# gps.net
KiCad netlist of a schematic drawn in Altium Designer
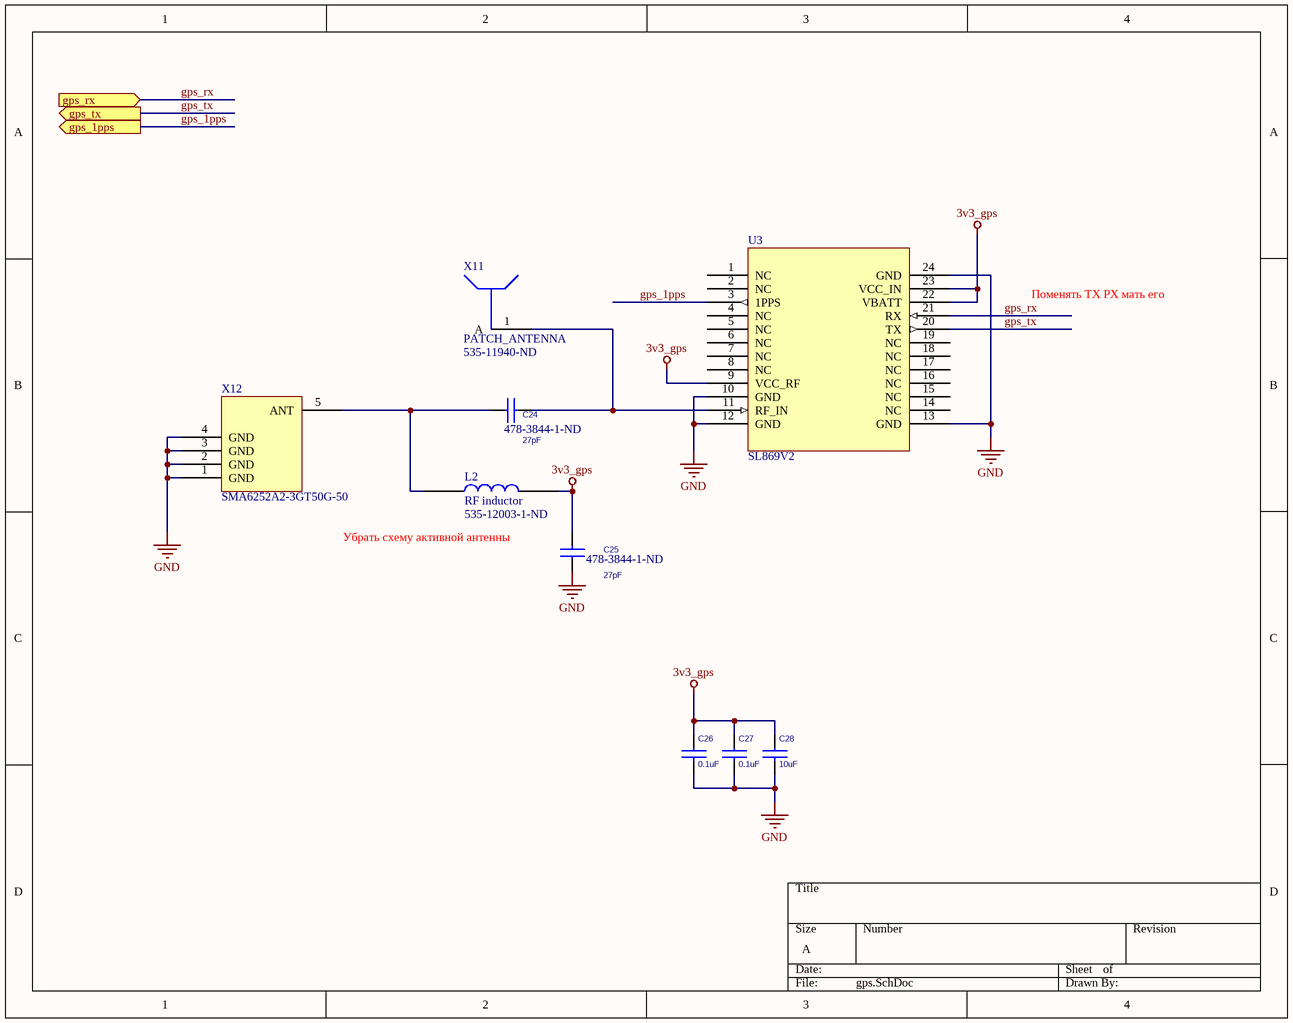
[diagram p0: gps.SchDoc]

(export (version "E")
  (design (tool "Eeschema 10.0.6"))
  (components
    (comp (ref "C24")
      (value "27pF")
      (footprint "CAPC2012X09M")
      (description "CAP CER 27PF 200V 5% NP0 0805")
      (fields (field (name "SUPPLIER PART NUMBER 1") "478-3844-1-ND"))
      (libsource (lib "Capacitors") (part "CAP_SMD_27PF_5%"))
    )
    (comp (ref "C25")
      (value "27pF")
      (footprint "CAPC2012X09M")
      (description "CAP CER 27PF 200V 5% NP0 0805")
      (fields (field (name "SUPPLIER PART NUMBER 1") "478-3844-1-ND"))
      (libsource (lib "Capacitors") (part "CAP_SMD_27PF_5%"))
    )
    (comp (ref "C26")
      (value "0.1uF")
      (footprint "CAPC2012X09M")
      (description "CAP CER 0.1UF 25V 10% X7R 0805")
      (libsource (lib "Capacitors") (part "CAP_SMD_0.1UF_10%"))
    )
    (comp (ref "C27")
      (value "0.1uF")
      (footprint "CAPC2012X09M")
      (description "CAP CER 0.1UF 25V 10% X7R 0805")
      (libsource (lib "Capacitors") (part "CAP_SMD_0.1UF_10%"))
    )
    (comp (ref "C28")
      (value "10uF")
      (footprint "CAPC2012X09M")
      (description "CAP CER 10UF 16V 20% X5R 0805")
      (libsource (lib "Capacitors") (part "CAP_SMD_10UF_20%"))
    )
    (comp (ref "L2")
      (value "RF inductor")
      (footprint "DIOC2012X11N_RF")
      (description "RF 35.5NH 1.5GHZ")
      (fields (field (name "SUPPLIER PART NUMBER 1") "535-12003-1-ND"))
      (libsource (lib "Passive") (part "RF_IND35.5nH"))
    )
    (comp (ref "U3")
      (value "SL869V2")
      (footprint "SL869V2_FOOT")
      (libsource (lib "TruthEar") (part "SL869V2"))
    )
    (comp (ref "X11")
      (value "PATCH_ANTENNA")
      (footprint "PATCH_ANTENNA")
      (fields (field (name "SUPPLIER PART NUMBER 1") "535-11940-ND"))
      (libsource (lib "TruthEar") (part "PATCH_ANTENNA"))
    )
    (comp (ref "X12")
      (value "SMA6252A2-3GT50G-50")
      (footprint "SMA6252A2-3GT50G-50")
      (libsource (lib "Connectors") (part "SMA_CONN"))
    )
  )
  (nets
    (net (code "1") (name "/gps_1pps") (class "Default")
      (node (ref "U3") (pin "3") (pinfunction "1PPS_3") (pintype "output"))
    )
    (net (code "2") (name "/gps_rx") (class "Default")
      (node (ref "U3") (pin "21") (pinfunction "RX_21") (pintype "input"))
    )
    (net (code "3") (name "/gps_tx") (class "Default")
      (node (ref "U3") (pin "20") (pinfunction "TX_20") (pintype "output"))
    )
    (net (code "4") (name "3v3_gps") (class "Default")
      (node (ref "C25") (pin "2") (pinfunction "2_2") (pintype "passive"))
      (node (ref "C26") (pin "1") (pinfunction "1_1") (pintype "passive"))
      (node (ref "C27") (pin "1") (pinfunction "1_1") (pintype "passive"))
      (node (ref "C28") (pin "1") (pinfunction "1_1") (pintype "passive"))
      (node (ref "L2") (pin "2") (pinfunction "2_2") (pintype "passive"))
      (node (ref "U3") (pin "22") (pinfunction "VBATT_22") (pintype "passive"))
      (node (ref "U3") (pin "23") (pinfunction "VCC_IN_23") (pintype "passive"))
      (node (ref "U3") (pin "9") (pinfunction "VCC_RF_9") (pintype "passive"))
    )
    (net (code "5") (name "GND") (class "Default")
      (node (ref "C25") (pin "1") (pinfunction "1_1") (pintype "passive"))
      (node (ref "C26") (pin "2") (pinfunction "2_2") (pintype "passive"))
      (node (ref "C27") (pin "2") (pinfunction "2_2") (pintype "passive"))
      (node (ref "C28") (pin "2") (pinfunction "2_2") (pintype "passive"))
      (node (ref "U3") (pin "10") (pinfunction "GND_10") (pintype "passive"))
      (node (ref "U3") (pin "12") (pinfunction "GND_12") (pintype "passive"))
      (node (ref "U3") (pin "13") (pinfunction "GND_13") (pintype "passive"))
      (node (ref "U3") (pin "24") (pinfunction "GND_24") (pintype "passive"))
      (node (ref "X12") (pin "1") (pinfunction "GND_1") (pintype "passive"))
      (node (ref "X12") (pin "2") (pinfunction "GND_2") (pintype "passive"))
      (node (ref "X12") (pin "3") (pinfunction "GND_3") (pintype "passive"))
      (node (ref "X12") (pin "4") (pinfunction "GND_4") (pintype "passive"))
    )
    (net (code "6") (name "Net-(U3-RF_IN)") (class "Default")
      (node (ref "C24") (pin "2") (pinfunction "2_2") (pintype "passive"))
      (node (ref "U3") (pin "11") (pinfunction "RF_IN_11") (pintype "input"))
      (node (ref "X11") (pin "1") (pinfunction "A_1") (pintype "passive"))
    )
    (net (code "7") (name "Net-(X12-ANT)") (class "Default")
      (node (ref "C24") (pin "1") (pinfunction "1_1") (pintype "passive"))
      (node (ref "L2") (pin "1") (pinfunction "1_1") (pintype "passive"))
      (node (ref "X12") (pin "5") (pinfunction "ANT_5") (pintype "passive"))
    )
    (net (code "8") (name "unconnected-(U3-NC-Pad1)") (class "Default")
      (node (ref "U3") (pin "1") (pinfunction "NC_1") (pintype "passive"))
    )
    (net (code "9") (name "unconnected-(U3-NC-Pad2)") (class "Default")
      (node (ref "U3") (pin "2") (pinfunction "NC_2") (pintype "passive"))
    )
    (net (code "10") (name "unconnected-(U3-NC-Pad4)") (class "Default")
      (node (ref "U3") (pin "4") (pinfunction "NC_4") (pintype "passive"))
    )
    (net (code "11") (name "unconnected-(U3-NC-Pad5)") (class "Default")
      (node (ref "U3") (pin "5") (pinfunction "NC_5") (pintype "passive"))
    )
    (net (code "12") (name "unconnected-(U3-NC-Pad6)") (class "Default")
      (node (ref "U3") (pin "6") (pinfunction "NC_6") (pintype "passive"))
    )
    (net (code "13") (name "unconnected-(U3-NC-Pad7)") (class "Default")
      (node (ref "U3") (pin "7") (pinfunction "NC_7") (pintype "passive"))
    )
    (net (code "14") (name "unconnected-(U3-NC-Pad8)") (class "Default")
      (node (ref "U3") (pin "8") (pinfunction "NC_8") (pintype "passive"))
    )
    (net (code "15") (name "unconnected-(U3-NC-Pad14)") (class "Default")
      (node (ref "U3") (pin "14") (pinfunction "NC_14") (pintype "passive"))
    )
    (net (code "16") (name "unconnected-(U3-NC-Pad15)") (class "Default")
      (node (ref "U3") (pin "15") (pinfunction "NC_15") (pintype "passive"))
    )
    (net (code "17") (name "unconnected-(U3-NC-Pad16)") (class "Default")
      (node (ref "U3") (pin "16") (pinfunction "NC_16") (pintype "passive"))
    )
    (net (code "18") (name "unconnected-(U3-NC-Pad17)") (class "Default")
      (node (ref "U3") (pin "17") (pinfunction "NC_17") (pintype "passive"))
    )
    (net (code "19") (name "unconnected-(U3-NC-Pad18)") (class "Default")
      (node (ref "U3") (pin "18") (pinfunction "NC_18") (pintype "passive"))
    )
    (net (code "20") (name "unconnected-(U3-NC-Pad19)") (class "Default")
      (node (ref "U3") (pin "19") (pinfunction "NC_19") (pintype "passive"))
    )
  )
)
